# main.net
KiCad netlist of a schematic drawn in EAGLE
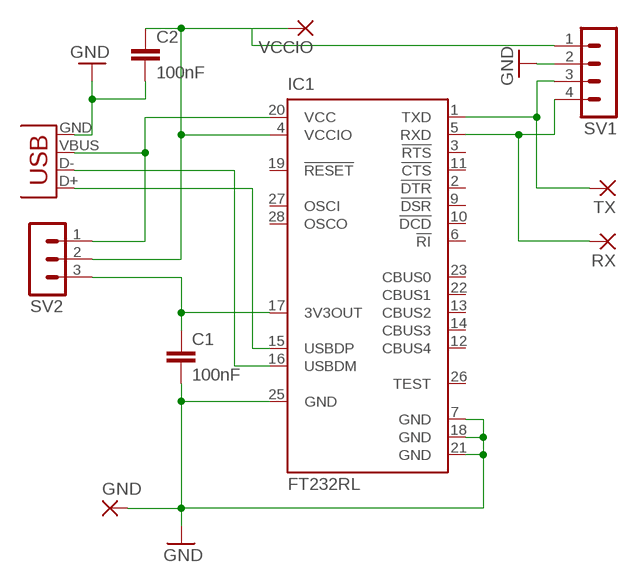
[diagram p0: schematic, sheet 1]

(export (version "E")
  (design (tool "Eeschema 10.0.6"))
  (components
    (comp (ref "C1")
      (value "100nF")
      (footprint "eagle-import:C0805")
      (libsource (lib "eagle-import") (part "C-EUC0805"))
    )
    (comp (ref "C2")
      (value "100nF")
      (footprint "eagle-import:C0805")
      (libsource (lib "eagle-import") (part "C-EUC0805"))
    )
    (comp (ref "GND")
      (value "WIREPADSMD1,27-254")
      (footprint "eagle-import:SMD1,27-2,54")
      (libsource (lib "eagle-import") (part "WIREPADSMD1,27-254"))
    )
    (comp (ref "IC1")
      (value "FT232RL")
      (footprint "eagle-import:SSOP28")
      (libsource (lib "eagle-import") (part "FT232RL"))
    )
    (comp (ref "RX")
      (value "WIREPADSMD1,27-254")
      (footprint "eagle-import:SMD1,27-2,54")
      (libsource (lib "eagle-import") (part "WIREPADSMD1,27-254"))
    )
    (comp (ref "SV1")
      (value "MA04-1")
      (footprint "eagle-import:MA04-1")
      (libsource (lib "eagle-import") (part "MA04-1"))
    )
    (comp (ref "SV2")
      (value "MA03-1")
      (footprint "eagle-import:MA03-1")
      (fields (field (name "OC_FARNELL") "unknown") (field (name "OC_NEWARK") "unknown"))
      (libsource (lib "eagle-import") (part "MA03-1"))
    )
    (comp (ref "TX")
      (value "WIREPADSMD1,27-254")
      (footprint "eagle-import:SMD1,27-2,54")
      (libsource (lib "eagle-import") (part "WIREPADSMD1,27-254"))
    )
    (comp (ref "VCCIO")
      (value "WIREPADSMD1,27-254")
      (footprint "eagle-import:SMD1,27-2,54")
      (libsource (lib "eagle-import") (part "WIREPADSMD1,27-254"))
    )
    (comp (ref "X1")
      (value "USB-MICROB")
      (footprint "eagle-import:USB-MICROB")
      (libsource (lib "eagle-import") (part "USB-MICROB"))
    )
  )
  (nets
    (net (code "1") (name "GND") (class "Default")
      (node (ref "C1") (pin "2") (pinfunction "2_2") (pintype "passive"))
      (node (ref "C2") (pin "2") (pinfunction "2_2") (pintype "passive"))
      (node (ref "GND") (pin "1") (pinfunction "P_1") (pintype "passive"))
      (node (ref "IC1") (pin "18") (pinfunction "GND_18") (pintype "power_in"))
      (node (ref "IC1") (pin "21") (pinfunction "GND_21") (pintype "power_in"))
      (node (ref "IC1") (pin "25") (pinfunction "GND_25") (pintype "power_in"))
      (node (ref "IC1") (pin "7") (pinfunction "GND_7") (pintype "power_in"))
      (node (ref "SV1") (pin "2") (pinfunction "2_2") (pintype "passive"))
      (node (ref "X1") (pin "GND") (pinfunction "GND_GND") (pintype "bidirectional"))
    )
    (net (code "2") (name "Net-(IC1-3V3OUT)") (class "Default")
      (node (ref "C1") (pin "1") (pinfunction "1_1") (pintype "passive"))
      (node (ref "IC1") (pin "17") (pinfunction "3V3OUT_17") (pintype "output"))
      (node (ref "SV2") (pin "3") (pinfunction "3_3") (pintype "passive"))
    )
    (net (code "3") (name "Net-(IC1-RXD)") (class "Default")
      (node (ref "IC1") (pin "5") (pinfunction "RXD_5") (pintype "input"))
      (node (ref "RX") (pin "1") (pinfunction "P_1") (pintype "passive"))
      (node (ref "SV1") (pin "4") (pinfunction "4_4") (pintype "passive"))
    )
    (net (code "4") (name "Net-(IC1-TXD)") (class "Default")
      (node (ref "IC1") (pin "1") (pinfunction "TXD_1") (pintype "output"))
      (node (ref "SV1") (pin "3") (pinfunction "3_3") (pintype "passive"))
      (node (ref "TX") (pin "1") (pinfunction "P_1") (pintype "passive"))
    )
    (net (code "5") (name "Net-(IC1-USBDM)") (class "Default")
      (node (ref "IC1") (pin "16") (pinfunction "USBDM_16") (pintype "bidirectional"))
      (node (ref "X1") (pin "D-") (pinfunction "D-_D-") (pintype "bidirectional"))
    )
    (net (code "6") (name "Net-(IC1-USBDP)") (class "Default")
      (node (ref "IC1") (pin "15") (pinfunction "USBDP_15") (pintype "bidirectional"))
      (node (ref "X1") (pin "D+") (pinfunction "D+_D+") (pintype "bidirectional"))
    )
    (net (code "7") (name "Net-(IC1-VCC)") (class "Default")
      (node (ref "IC1") (pin "20") (pinfunction "VCC_20") (pintype "power_in"))
      (node (ref "SV2") (pin "1") (pinfunction "1_1") (pintype "passive"))
      (node (ref "X1") (pin "VBUS") (pinfunction "VBUS_VBUS") (pintype "bidirectional"))
    )
    (net (code "8") (name "Net-(IC1-VCCIO)") (class "Default")
      (node (ref "C2") (pin "1") (pinfunction "1_1") (pintype "passive"))
      (node (ref "IC1") (pin "4") (pinfunction "VCCIO_4") (pintype "power_in"))
      (node (ref "SV1") (pin "1") (pinfunction "1_1") (pintype "passive"))
      (node (ref "SV2") (pin "2") (pinfunction "2_2") (pintype "passive"))
      (node (ref "VCCIO") (pin "1") (pinfunction "P_1") (pintype "passive"))
    )
    (net (code "9") (name "unconnected-(IC1-CBUS0-Pad23)") (class "Default")
      (node (ref "IC1") (pin "23") (pinfunction "CBUS0_23") (pintype "bidirectional"))
    )
    (net (code "10") (name "unconnected-(IC1-CBUS1-Pad22)") (class "Default")
      (node (ref "IC1") (pin "22") (pinfunction "CBUS1_22") (pintype "bidirectional"))
    )
    (net (code "11") (name "unconnected-(IC1-CBUS2-Pad13)") (class "Default")
      (node (ref "IC1") (pin "13") (pinfunction "CBUS2_13") (pintype "bidirectional"))
    )
    (net (code "12") (name "unconnected-(IC1-CBUS3-Pad14)") (class "Default")
      (node (ref "IC1") (pin "14") (pinfunction "CBUS3_14") (pintype "bidirectional"))
    )
    (net (code "13") (name "unconnected-(IC1-CBUS4-Pad12)") (class "Default")
      (node (ref "IC1") (pin "12") (pinfunction "CBUS4_12") (pintype "bidirectional"))
    )
    (net (code "14") (name "unconnected-(IC1-OSCI-Pad27)") (class "Default")
      (node (ref "IC1") (pin "27") (pinfunction "OSCI_27") (pintype "input"))
    )
    (net (code "15") (name "unconnected-(IC1-OSCO-Pad28)") (class "Default")
      (node (ref "IC1") (pin "28") (pinfunction "OSCO_28") (pintype "output"))
    )
    (net (code "16") (name "unconnected-(IC1-TEST-Pad26)") (class "Default")
      (node (ref "IC1") (pin "26") (pinfunction "TEST_26") (pintype "input"))
    )
    (net (code "17") (name "unconnected-(IC1-~{CTS}-Pad11)") (class "Default")
      (node (ref "IC1") (pin "11") (pinfunction "~{CTS}_11") (pintype "input"))
    )
    (net (code "18") (name "unconnected-(IC1-~{DCD}-Pad10)") (class "Default")
      (node (ref "IC1") (pin "10") (pinfunction "~{DCD}_10") (pintype "input"))
    )
    (net (code "19") (name "unconnected-(IC1-~{DSR}-Pad9)") (class "Default")
      (node (ref "IC1") (pin "9") (pinfunction "~{DSR}_9") (pintype "input"))
    )
    (net (code "20") (name "unconnected-(IC1-~{DTR}-Pad2)") (class "Default")
      (node (ref "IC1") (pin "2") (pinfunction "~{DTR}_2") (pintype "output"))
    )
    (net (code "21") (name "unconnected-(IC1-~{RESET}-Pad19)") (class "Default")
      (node (ref "IC1") (pin "19") (pinfunction "~{RESET}_19") (pintype "input"))
    )
    (net (code "22") (name "unconnected-(IC1-~{RI}-Pad6)") (class "Default")
      (node (ref "IC1") (pin "6") (pinfunction "~{RI}_6") (pintype "input"))
    )
    (net (code "23") (name "unconnected-(IC1-~{RTS}-Pad3)") (class "Default")
      (node (ref "IC1") (pin "3") (pinfunction "~{RTS}_3") (pintype "output"))
    )
  )
)
